# Sheet_Amp_1.net
KiCad netlist of a schematic drawn in Altium Designer
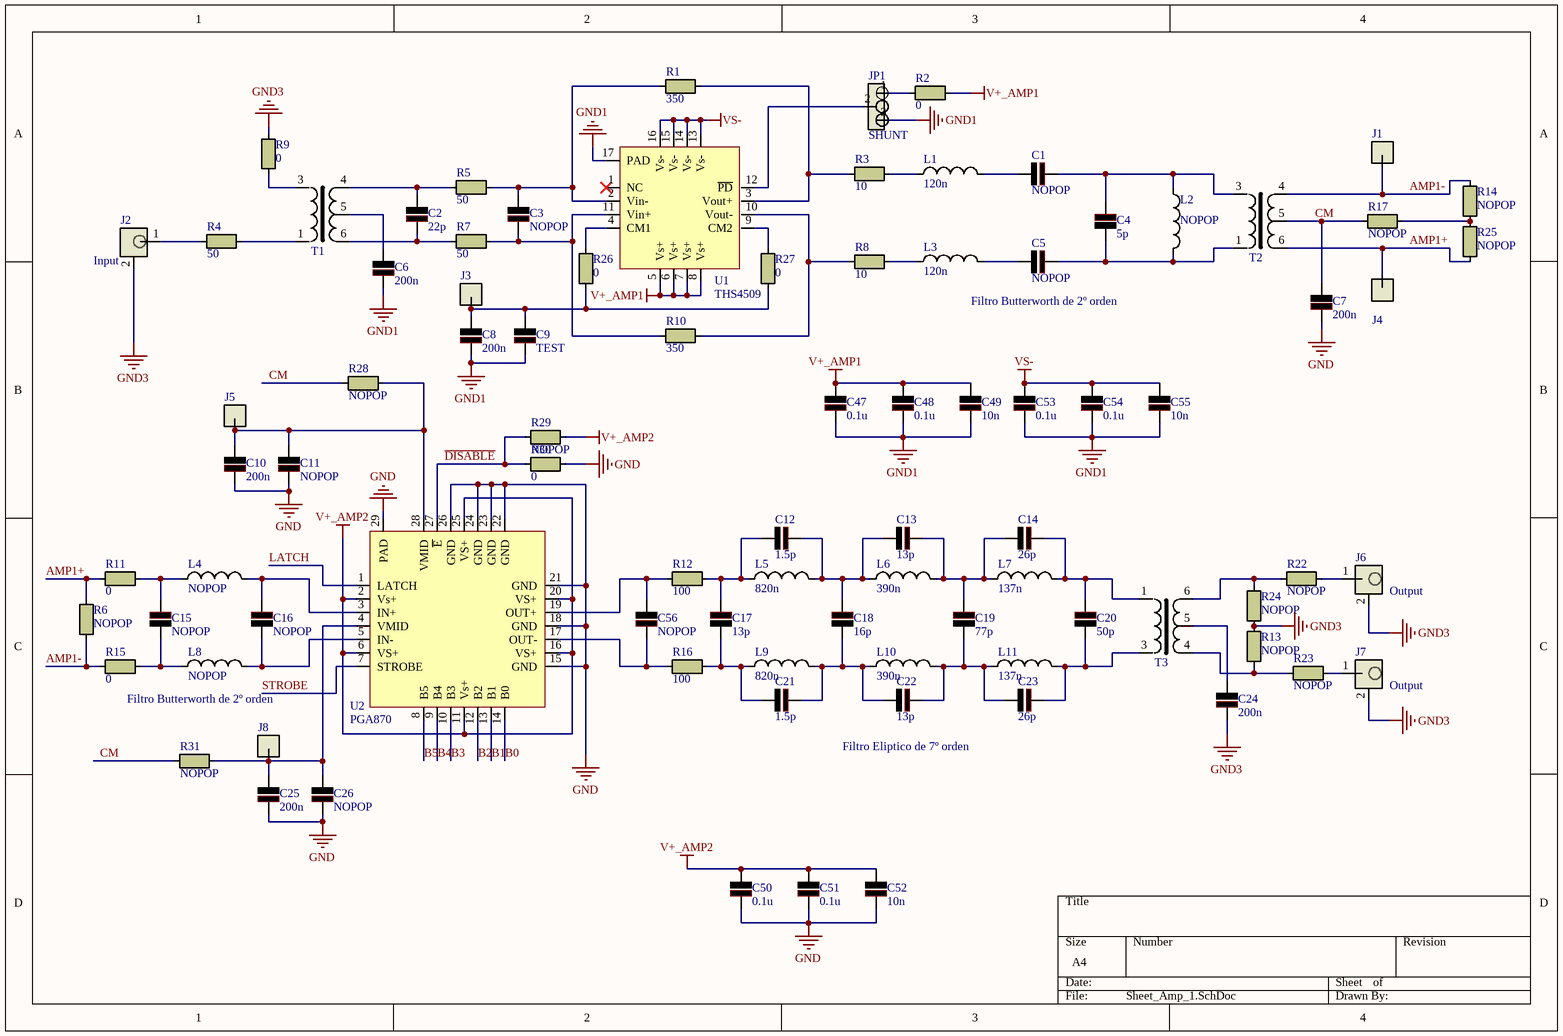
[diagram p0: Sheet_Amp_1.SchDoc]

(export (version "E")
  (design (tool "Eeschema 10.0.6"))
  (components
    (comp (ref "C1") (value "NOPOP") (footprint "C_0603") (libsource (lib "") (part "C_2")))
    (comp (ref "C2") (value "22p") (footprint "C_0603") (libsource (lib "Alberto_Sch") (part "C")))
    (comp (ref "C3") (value "NOPOP") (footprint "C_0603") (libsource (lib "Alberto_Sch") (part "C")))
    (comp (ref "C4") (value "5p") (footprint "C_0603") (libsource (lib "") (part "C_1")))
    (comp (ref "C5") (value "NOPOP") (footprint "C_0603") (libsource (lib "") (part "C_2")))
    (comp (ref "C6") (value "200n") (footprint "C_0603") (libsource (lib "Alberto_Sch") (part "C")))
    (comp (ref "C7") (value "200n") (footprint "C_0603") (libsource (lib "Alberto_Sch") (part "C")))
    (comp (ref "C8") (value "200n") (footprint "C_0805") (libsource (lib "Alberto_Sch") (part "C")))
    (comp (ref "C9") (value "TEST") (footprint "C_0805") (libsource (lib "Alberto_Sch") (part "C")))
    (comp (ref "C10") (value "200n") (footprint "C_0805") (libsource (lib "Alberto_Sch") (part "C")))
    (comp (ref "C11") (value "NOPOP") (footprint "C_0805") (libsource (lib "Alberto_Sch") (part "C")))
    (comp (ref "C12") (value "1.5p") (footprint "C_0603") (libsource (lib "") (part "C_2")))
    (comp (ref "C13") (value "13p") (footprint "C_0603") (libsource (lib "") (part "C_2")))
    (comp (ref "C14") (value "26p") (footprint "C_0603") (libsource (lib "") (part "C_2")))
    (comp (ref "C15") (value "NOPOP") (footprint "C_0603") (libsource (lib "") (part "C_1")))
    (comp (ref "C16") (value "NOPOP") (footprint "C_0603") (libsource (lib "") (part "C_1")))
    (comp (ref "C17") (value "13p") (footprint "C_0603") (libsource (lib "") (part "C_1")))
    (comp (ref "C18") (value "16p") (footprint "C_0603") (libsource (lib "") (part "C_1")))
    (comp (ref "C19") (value "77p") (footprint "C_0603") (libsource (lib "") (part "C_1")))
    (comp (ref "C20") (value "50p") (footprint "C_0603") (libsource (lib "") (part "C_1")))
    (comp (ref "C21") (value "1.5p") (footprint "C_0603") (libsource (lib "") (part "C_2")))
    (comp (ref "C22") (value "13p") (footprint "C_0603") (libsource (lib "") (part "C_2")))
    (comp (ref "C23") (value "26p") (footprint "C_0603") (libsource (lib "") (part "C_2")))
    (comp (ref "C24") (value "200n") (footprint "C_0603") (libsource (lib "Alberto_Sch") (part "C")))
    (comp (ref "C25") (value "200n") (footprint "C_0805") (libsource (lib "Alberto_Sch") (part "C")))
    (comp (ref "C26") (value "NOPOP") (footprint "C_0805") (libsource (lib "Alberto_Sch") (part "C")))
    (comp (ref "C47") (value "0.1u") (footprint "C_0805") (libsource (lib "Alberto_Sch") (part "C")))
    (comp (ref "C48") (value "0.1u") (footprint "C_0805") (libsource (lib "Alberto_Sch") (part "C")))
    (comp (ref "C49") (value "10n") (footprint "C_0805") (libsource (lib "Alberto_Sch") (part "C")))
    (comp (ref "C50") (value "0.1u") (footprint "C_0805") (libsource (lib "Alberto_Sch") (part "C")))
    (comp (ref "C51") (value "0.1u") (footprint "C_0805") (libsource (lib "Alberto_Sch") (part "C")))
    (comp (ref "C52") (value "10n") (footprint "C_0805") (libsource (lib "Alberto_Sch") (part "C")))
    (comp (ref "C53") (value "0.1u") (footprint "C_0805") (libsource (lib "Alberto_Sch") (part "C")))
    (comp (ref "C54") (value "0.1u") (footprint "C_0805") (libsource (lib "Alberto_Sch") (part "C")))
    (comp (ref "C55") (value "10n") (footprint "C_0805") (libsource (lib "Alberto_Sch") (part "C")))
    (comp (ref "C56") (value "NOPOP") (footprint "C_0603") (libsource (lib "Alberto_Sch") (part "C")))
    (comp (ref "J1")
      (value "TEST POINT")
      (footprint "TEST_Point")
      (libsource (lib "Alberto_Sch") (part "TEST POINT"))
    )
    (comp (ref "J2") (value "Input") (footprint "BNC") (libsource (lib "Alberto_Sch") (part "Input")))
    (comp (ref "J3")
      (value "TEST POINT")
      (footprint "TEST_Point")
      (libsource (lib "Alberto_Sch") (part "TEST POINT"))
    )
    (comp (ref "J4") (value "TEST POINT") (footprint "TEST_Point") (libsource (lib "") (part "TEST POINT_1")))
    (comp (ref "J5")
      (value "TEST POINT")
      (footprint "TEST_Point")
      (libsource (lib "Alberto_Sch") (part "TEST POINT"))
    )
    (comp (ref "J6") (value "Output") (footprint "SMA") (libsource (lib "Alberto_Sch") (part "Output")))
    (comp (ref "J7") (value "Output") (footprint "SMA") (libsource (lib "Alberto_Sch") (part "Output")))
    (comp (ref "J8")
      (value "TEST POINT")
      (footprint "TEST_Point")
      (libsource (lib "Alberto_Sch") (part "TEST POINT"))
    )
    (comp (ref "JP1")
      (value "SHUNT")
      (footprint "JUMPER_2,54_3")
      (libsource (lib "Alberto_Sch") (part "SHUNT"))
    )
    (comp (ref "L1") (value "120n") (footprint "L_0603") (libsource (lib "Alberto_Sch") (part "L")))
    (comp (ref "L2") (value "NOPOP") (footprint "L_0603") (libsource (lib "Alberto_Sch") (part "L")))
    (comp (ref "L3") (value "120n") (footprint "L_0603") (libsource (lib "Alberto_Sch") (part "L")))
    (comp (ref "L4") (value "NOPOP") (footprint "L_0603") (libsource (lib "Alberto_Sch") (part "L")))
    (comp (ref "L5") (value "820n") (footprint "L_0603") (libsource (lib "Alberto_Sch") (part "L")))
    (comp (ref "L6") (value "390n") (footprint "L_0603") (libsource (lib "Alberto_Sch") (part "L")))
    (comp (ref "L7") (value "137n") (footprint "L_0603") (libsource (lib "Alberto_Sch") (part "L")))
    (comp (ref "L8") (value "NOPOP") (footprint "L_0603") (libsource (lib "Alberto_Sch") (part "L")))
    (comp (ref "L9") (value "820n") (footprint "L_0603") (libsource (lib "Alberto_Sch") (part "L")))
    (comp (ref "L10") (value "390n") (footprint "L_0603") (libsource (lib "Alberto_Sch") (part "L")))
    (comp (ref "L11") (value "137n") (footprint "L_0603") (libsource (lib "Alberto_Sch") (part "L")))
    (comp (ref "R1") (value "350") (footprint "R_0603") (libsource (lib "Alberto_Sch") (part "R")))
    (comp (ref "R2") (value "0") (footprint "R_0603") (libsource (lib "Alberto_Sch") (part "R")))
    (comp (ref "R3") (value "10") (footprint "R_0603") (libsource (lib "Alberto_Sch") (part "R")))
    (comp (ref "R4") (value "50") (footprint "R_0603") (libsource (lib "Alberto_Sch") (part "R")))
    (comp (ref "R5") (value "50") (footprint "R_0603") (libsource (lib "Alberto_Sch") (part "R")))
    (comp (ref "R6") (value "NOPOP") (footprint "R_0603") (libsource (lib "") (part "R_1")))
    (comp (ref "R7") (value "50") (footprint "R_0603") (libsource (lib "Alberto_Sch") (part "R")))
    (comp (ref "R8") (value "10") (footprint "R_0603") (libsource (lib "Alberto_Sch") (part "R")))
    (comp (ref "R9") (value "0") (footprint "R_0603") (libsource (lib "") (part "R_1")))
    (comp (ref "R10") (value "350") (footprint "R_0603") (libsource (lib "Alberto_Sch") (part "R")))
    (comp (ref "R11") (value "0") (footprint "R_0603") (libsource (lib "Alberto_Sch") (part "R")))
    (comp (ref "R12") (value "100") (footprint "R_0603") (libsource (lib "Alberto_Sch") (part "R")))
    (comp (ref "R13") (value "NOPOP") (footprint "R_0603") (libsource (lib "") (part "R_1")))
    (comp (ref "R14") (value "NOPOP") (footprint "R_0603") (libsource (lib "") (part "R_1")))
    (comp (ref "R15") (value "0") (footprint "R_0603") (libsource (lib "Alberto_Sch") (part "R")))
    (comp (ref "R16") (value "100") (footprint "R_0603") (libsource (lib "Alberto_Sch") (part "R")))
    (comp (ref "R17") (value "NOPOP") (footprint "R_0603") (libsource (lib "") (part "R_2")))
    (comp (ref "R22") (value "NOPOP") (footprint "R_0603") (libsource (lib "Alberto_Sch") (part "R")))
    (comp (ref "R23") (value "NOPOP") (footprint "R_0603") (libsource (lib "Alberto_Sch") (part "R")))
    (comp (ref "R24") (value "NOPOP") (footprint "R_0603") (libsource (lib "") (part "R_1")))
    (comp (ref "R25") (value "NOPOP") (footprint "R_0603") (libsource (lib "") (part "R_1")))
    (comp (ref "R26") (value "0") (footprint "R_0603") (libsource (lib "") (part "R_1")))
    (comp (ref "R27") (value "0") (footprint "R_0603") (libsource (lib "") (part "R_1")))
    (comp (ref "R28") (value "NOPOP") (footprint "R_0603") (libsource (lib "Alberto_Sch") (part "R")))
    (comp (ref "R29") (value "NOPOP") (footprint "R_0603") (libsource (lib "Alberto_Sch") (part "R")))
    (comp (ref "R30") (value "0") (footprint "R_0603") (libsource (lib "Alberto_Sch") (part "R")))
    (comp (ref "R31") (value "NOPOP") (footprint "R_0603") (libsource (lib "Alberto_Sch") (part "R")))
    (comp (ref "T1")
      (value "ADT1-1WT")
      (footprint "TRASFORMADOR_2.54")
      (libsource (lib "Alberto_Sch") (part "Transformer_center_tab"))
    )
    (comp (ref "T2")
      (value "ADT1-1WT")
      (footprint "TRASFORMADOR_2.54")
      (libsource (lib "Alberto_Sch") (part "Transformer_center_tab"))
    )
    (comp (ref "T3")
      (value "ADT1-1WT")
      (footprint "TRASFORMADOR_2.54")
      (libsource (lib "") (part "Transformer_center_tab_1"))
    )
    (comp (ref "U1") (value "THS4509") (footprint "QFN_16") (libsource (lib "Alberto_Sch") (part "THS4509")))
    (comp (ref "U2") (value "PGA870") (footprint "QFN_28") (libsource (lib "Alberto_Sch") (part "PGA870")))
  )
  (nets
    (net (code "1") (name "/AMP1+") (class "Default")
      (node (ref "J4") (pin "1") (pinfunction "1_1") (pintype "passive"))
      (node (ref "R11") (pin "1") (pintype "passive"))
      (node (ref "R25") (pin "1") (pintype "passive"))
      (node (ref "R6") (pin "2") (pintype "passive"))
      (node (ref "T2") (pin "6") (pinfunction "6_6") (pintype "passive"))
    )
    (net (code "2") (name "/AMP1-") (class "Default")
      (node (ref "J1") (pin "1") (pinfunction "1_1") (pintype "passive"))
      (node (ref "R14") (pin "2") (pintype "passive"))
      (node (ref "R15") (pin "1") (pintype "passive"))
      (node (ref "R6") (pin "1") (pintype "passive"))
      (node (ref "T2") (pin "4") (pinfunction "4_4") (pintype "passive"))
    )
    (net (code "3") (name "/B0") (class "Default")
      (node (ref "U2") (pin "14") (pinfunction "B0_14") (pintype "passive"))
    )
    (net (code "4") (name "/B1") (class "Default")
      (node (ref "U2") (pin "13") (pinfunction "B1_13") (pintype "passive"))
    )
    (net (code "5") (name "/B2") (class "Default")
      (node (ref "U2") (pin "12") (pinfunction "B2_12") (pintype "passive"))
    )
    (net (code "6") (name "/B3") (class "Default")
      (node (ref "U2") (pin "10") (pinfunction "B3_10") (pintype "passive"))
    )
    (net (code "7") (name "/B4") (class "Default")
      (node (ref "U2") (pin "9") (pinfunction "B4_9") (pintype "passive"))
    )
    (net (code "8") (name "/B5") (class "Default")
      (node (ref "U2") (pin "8") (pinfunction "B5_8") (pintype "passive"))
    )
    (net (code "9") (name "/CM") (class "Default")
      (node (ref "C7") (pin "1") (pintype "passive"))
      (node (ref "R17") (pin "2") (pintype "passive"))
      (node (ref "R28") (pin "1") (pintype "passive"))
      (node (ref "R31") (pin "1") (pintype "passive"))
      (node (ref "T2") (pin "5") (pinfunction "5_5") (pintype "passive"))
    )
    (net (code "10") (name "/LATCH") (class "Default")
      (node (ref "U2") (pin "1") (pinfunction "LATCH_1") (pintype "passive"))
    )
    (net (code "11") (name "/STROBE") (class "Default")
      (node (ref "U2") (pin "7") (pinfunction "STROBE_7") (pintype "passive"))
    )
    (net (code "12") (name "/~{DISABLE}") (class "Default")
      (node (ref "R29") (pin "1") (pintype "passive"))
      (node (ref "R30") (pin "1") (pintype "passive"))
      (node (ref "U2") (pin "27") (pinfunction "~{E}_27") (pintype "passive"))
    )
    (net (code "13") (name "GND") (class "Default")
      (node (ref "C10") (pin "2") (pintype "passive"))
      (node (ref "C11") (pin "2") (pintype "passive"))
      (node (ref "C25") (pin "2") (pintype "passive"))
      (node (ref "C26") (pin "2") (pintype "passive"))
      (node (ref "C50") (pin "2") (pintype "passive"))
      (node (ref "C51") (pin "2") (pintype "passive"))
      (node (ref "C52") (pin "2") (pintype "passive"))
      (node (ref "C7") (pin "2") (pintype "passive"))
      (node (ref "R30") (pin "2") (pintype "passive"))
      (node (ref "U2") (pin "15") (pinfunction "GND_15") (pintype "passive"))
      (node (ref "U2") (pin "18") (pinfunction "GND_18") (pintype "passive"))
      (node (ref "U2") (pin "21") (pinfunction "GND_21") (pintype "passive"))
      (node (ref "U2") (pin "22") (pinfunction "GND_22") (pintype "passive"))
      (node (ref "U2") (pin "23") (pinfunction "GND_23") (pintype "passive"))
      (node (ref "U2") (pin "24") (pinfunction "GND_24") (pintype "passive"))
      (node (ref "U2") (pin "26") (pinfunction "GND_26") (pintype "passive"))
      (node (ref "U2") (pin "29") (pinfunction "PAD_29") (pintype "passive"))
    )
    (net (code "14") (name "GND1") (class "Default")
      (node (ref "C47") (pin "2") (pintype "passive"))
      (node (ref "C48") (pin "2") (pintype "passive"))
      (node (ref "C49") (pin "2") (pintype "passive"))
      (node (ref "C53") (pin "2") (pintype "passive"))
      (node (ref "C54") (pin "2") (pintype "passive"))
      (node (ref "C55") (pin "2") (pintype "passive"))
      (node (ref "C6") (pin "2") (pintype "passive"))
      (node (ref "C8") (pin "2") (pintype "passive"))
      (node (ref "C9") (pin "2") (pintype "passive"))
      (node (ref "JP1") (pin "3") (pinfunction "3_3") (pintype "passive"))
      (node (ref "U1") (pin "17") (pinfunction "PAD_17") (pintype "passive"))
    )
    (net (code "15") (name "GND3") (class "Default")
      (node (ref "C24") (pin "2") (pintype "passive"))
      (node (ref "J2") (pin "2") (pinfunction "2_2") (pintype "passive"))
      (node (ref "J6") (pin "2") (pinfunction "2_2") (pintype "passive"))
      (node (ref "J7") (pin "2") (pinfunction "2_2") (pintype "passive"))
      (node (ref "R13") (pin "2") (pintype "passive"))
      (node (ref "R24") (pin "1") (pintype "passive"))
      (node (ref "R9") (pin "2") (pintype "passive"))
    )
    (net (code "16") (name "Net-(C1-Pad1)") (class "Default")
      (node (ref "C1") (pin "1") (pintype "passive"))
      (node (ref "L1") (pin "2") (pintype "passive"))
    )
    (net (code "17") (name "Net-(C1-Pad2)") (class "Default")
      (node (ref "C1") (pin "2") (pintype "passive"))
      (node (ref "C4") (pin "2") (pintype "passive"))
      (node (ref "L2") (pin "1") (pintype "passive"))
      (node (ref "T2") (pin "3") (pinfunction "3_3") (pintype "passive"))
    )
    (net (code "18") (name "Net-(C2-Pad1)") (class "Default")
      (node (ref "C2") (pin "1") (pintype "passive"))
      (node (ref "R5") (pin "1") (pintype "passive"))
      (node (ref "T1") (pin "4") (pinfunction "4_4") (pintype "passive"))
    )
    (net (code "19") (name "Net-(C2-Pad2)") (class "Default")
      (node (ref "C2") (pin "2") (pintype "passive"))
      (node (ref "R7") (pin "1") (pintype "passive"))
      (node (ref "T1") (pin "6") (pinfunction "6_6") (pintype "passive"))
    )
    (net (code "20") (name "Net-(C4-Pad1)") (class "Default")
      (node (ref "C4") (pin "1") (pintype "passive"))
      (node (ref "C5") (pin "2") (pintype "passive"))
      (node (ref "L2") (pin "2") (pintype "passive"))
      (node (ref "T2") (pin "1") (pinfunction "1_1") (pintype "passive"))
    )
    (net (code "21") (name "Net-(C5-Pad1)") (class "Default")
      (node (ref "C5") (pin "1") (pintype "passive"))
      (node (ref "L3") (pin "2") (pintype "passive"))
    )
    (net (code "22") (name "Net-(C6-Pad1)") (class "Default")
      (node (ref "C6") (pin "1") (pintype "passive"))
      (node (ref "T1") (pin "5") (pinfunction "5_5") (pintype "passive"))
    )
    (net (code "23") (name "Net-(C8-Pad1)") (class "Default")
      (node (ref "C8") (pin "1") (pintype "passive"))
      (node (ref "C9") (pin "1") (pintype "passive"))
      (node (ref "J3") (pin "1") (pinfunction "1_1") (pintype "passive"))
      (node (ref "R26") (pin "1") (pintype "passive"))
      (node (ref "R27") (pin "1") (pintype "passive"))
    )
    (net (code "24") (name "Net-(C10-Pad1)") (class "Default")
      (node (ref "C10") (pin "1") (pintype "passive"))
      (node (ref "C11") (pin "1") (pintype "passive"))
      (node (ref "J5") (pin "1") (pinfunction "1_1") (pintype "passive"))
      (node (ref "R28") (pin "2") (pintype "passive"))
      (node (ref "U2") (pin "28") (pinfunction "VMID_28") (pintype "passive"))
    )
    (net (code "25") (name "Net-(C12-Pad1)") (class "Default")
      (node (ref "C12") (pin "1") (pintype "passive"))
      (node (ref "C17") (pin "2") (pintype "passive"))
      (node (ref "L5") (pin "1") (pintype "passive"))
      (node (ref "R12") (pin "2") (pintype "passive"))
    )
    (net (code "26") (name "Net-(C12-Pad2)") (class "Default")
      (node (ref "C12") (pin "2") (pintype "passive"))
      (node (ref "C13") (pin "1") (pintype "passive"))
      (node (ref "C18") (pin "2") (pintype "passive"))
      (node (ref "L5") (pin "2") (pintype "passive"))
      (node (ref "L6") (pin "1") (pintype "passive"))
    )
    (net (code "27") (name "Net-(C13-Pad2)") (class "Default")
      (node (ref "C13") (pin "2") (pintype "passive"))
      (node (ref "C14") (pin "1") (pintype "passive"))
      (node (ref "C19") (pin "2") (pintype "passive"))
      (node (ref "L6") (pin "2") (pintype "passive"))
      (node (ref "L7") (pin "1") (pintype "passive"))
    )
    (net (code "28") (name "Net-(C14-Pad2)") (class "Default")
      (node (ref "C14") (pin "2") (pintype "passive"))
      (node (ref "C20") (pin "2") (pintype "passive"))
      (node (ref "L7") (pin "2") (pintype "passive"))
      (node (ref "T3") (pin "1") (pinfunction "1_1") (pintype "passive"))
    )
    (net (code "29") (name "Net-(C15-Pad1)") (class "Default")
      (node (ref "C15") (pin "1") (pintype "passive"))
      (node (ref "L8") (pin "1") (pintype "passive"))
      (node (ref "R15") (pin "2") (pintype "passive"))
    )
    (net (code "30") (name "Net-(C15-Pad2)") (class "Default")
      (node (ref "C15") (pin "2") (pintype "passive"))
      (node (ref "L4") (pin "1") (pintype "passive"))
      (node (ref "R11") (pin "2") (pintype "passive"))
    )
    (net (code "31") (name "Net-(C17-Pad1)") (class "Default")
      (node (ref "C17") (pin "1") (pintype "passive"))
      (node (ref "C21") (pin "1") (pintype "passive"))
      (node (ref "L9") (pin "1") (pintype "passive"))
      (node (ref "R16") (pin "2") (pintype "passive"))
    )
    (net (code "32") (name "Net-(C18-Pad1)") (class "Default")
      (node (ref "C18") (pin "1") (pintype "passive"))
      (node (ref "C21") (pin "2") (pintype "passive"))
      (node (ref "C22") (pin "1") (pintype "passive"))
      (node (ref "L10") (pin "1") (pintype "passive"))
      (node (ref "L9") (pin "2") (pintype "passive"))
    )
    (net (code "33") (name "Net-(C19-Pad1)") (class "Default")
      (node (ref "C19") (pin "1") (pintype "passive"))
      (node (ref "C22") (pin "2") (pintype "passive"))
      (node (ref "C23") (pin "1") (pintype "passive"))
      (node (ref "L10") (pin "2") (pintype "passive"))
      (node (ref "L11") (pin "1") (pintype "passive"))
    )
    (net (code "34") (name "Net-(C20-Pad1)") (class "Default")
      (node (ref "C20") (pin "1") (pintype "passive"))
      (node (ref "C23") (pin "2") (pintype "passive"))
      (node (ref "L11") (pin "2") (pintype "passive"))
      (node (ref "T3") (pin "3") (pinfunction "3_3") (pintype "passive"))
    )
    (net (code "35") (name "Net-(C24-Pad1)") (class "Default")
      (node (ref "C24") (pin "1") (pintype "passive"))
      (node (ref "T3") (pin "5") (pinfunction "5_5") (pintype "passive"))
    )
    (net (code "36") (name "Net-(C25-Pad1)") (class "Default")
      (node (ref "C25") (pin "1") (pintype "passive"))
      (node (ref "C26") (pin "1") (pintype "passive"))
      (node (ref "J8") (pin "1") (pinfunction "1_1") (pintype "passive"))
      (node (ref "R31") (pin "2") (pintype "passive"))
      (node (ref "U2") (pin "4") (pinfunction "VMID_4") (pintype "passive"))
    )
    (net (code "37") (name "Net-(J2-Pad1)") (class "Default")
      (node (ref "J2") (pin "1") (pinfunction "1_1") (pintype "passive"))
      (node (ref "R4") (pin "1") (pintype "passive"))
    )
    (net (code "38") (name "Net-(J6-Pad1)") (class "Default")
      (node (ref "J6") (pin "1") (pinfunction "1_1") (pintype "passive"))
      (node (ref "R22") (pin "2") (pintype "passive"))
    )
    (net (code "39") (name "Net-(J7-Pad1)") (class "Default")
      (node (ref "J7") (pin "1") (pinfunction "1_1") (pintype "passive"))
      (node (ref "R23") (pin "2") (pintype "passive"))
    )
    (net (code "40") (name "Net-(JP1-Pad1)") (class "Default")
      (node (ref "JP1") (pin "1") (pinfunction "1_1") (pintype "passive"))
      (node (ref "R2") (pin "1") (pintype "passive"))
    )
    (net (code "41") (name "Net-(L1-Pad1)") (class "Default")
      (node (ref "L1") (pin "1") (pintype "passive"))
      (node (ref "R3") (pin "2") (pintype "passive"))
    )
    (net (code "42") (name "Net-(L3-Pad1)") (class "Default")
      (node (ref "L3") (pin "1") (pintype "passive"))
      (node (ref "R8") (pin "2") (pintype "passive"))
    )
    (net (code "43") (name "Net-(R4-Pad2)") (class "Default")
      (node (ref "R4") (pin "2") (pintype "passive"))
      (node (ref "T1") (pin "1") (pinfunction "1_1") (pintype "passive"))
    )
    (net (code "44") (name "Net-(R9-Pad1)") (class "Default")
      (node (ref "R9") (pin "1") (pintype "passive"))
      (node (ref "T1") (pin "3") (pinfunction "3_3") (pintype "passive"))
    )
    (net (code "45") (name "Net-(R13-Pad1)") (class "Default")
      (node (ref "R13") (pin "1") (pintype "passive"))
      (node (ref "R23") (pin "1") (pintype "passive"))
      (node (ref "T3") (pin "4") (pinfunction "4_4") (pintype "passive"))
    )
    (net (code "46") (name "Net-(R14-Pad1)") (class "Default")
      (node (ref "R14") (pin "1") (pintype "passive"))
      (node (ref "R17") (pin "1") (pintype "passive"))
      (node (ref "R25") (pin "2") (pintype "passive"))
    )
    (net (code "47") (name "Net-(R22-Pad1)") (class "Default")
      (node (ref "R22") (pin "1") (pintype "passive"))
      (node (ref "R24") (pin "2") (pintype "passive"))
      (node (ref "T3") (pin "6") (pinfunction "6_6") (pintype "passive"))
    )
    (net (code "48") (name "Net-(U1-CM1)") (class "Default")
      (node (ref "R26") (pin "2") (pintype "passive"))
      (node (ref "U1") (pin "4") (pinfunction "CM1_4") (pintype "passive"))
    )
    (net (code "49") (name "Net-(U1-CM2)") (class "Default")
      (node (ref "R27") (pin "2") (pintype "passive"))
      (node (ref "U1") (pin "9") (pinfunction "CM2_9") (pintype "passive"))
    )
    (net (code "50") (name "Net-(U1-Vin+)") (class "Default")
      (node (ref "C3") (pin "2") (pintype "passive"))
      (node (ref "R10") (pin "1") (pintype "passive"))
      (node (ref "R7") (pin "2") (pintype "passive"))
      (node (ref "U1") (pin "11") (pinfunction "Vin+_11") (pintype "passive"))
    )
    (net (code "51") (name "Net-(U1-Vin-)") (class "Default")
      (node (ref "C3") (pin "1") (pintype "passive"))
      (node (ref "R1") (pin "1") (pintype "passive"))
      (node (ref "R5") (pin "2") (pintype "passive"))
      (node (ref "U1") (pin "2") (pinfunction "Vin-_2") (pintype "passive"))
    )
    (net (code "52") (name "Net-(U1-Vout+)") (class "Default")
      (node (ref "R1") (pin "2") (pintype "passive"))
      (node (ref "R3") (pin "1") (pintype "passive"))
      (node (ref "U1") (pin "3") (pinfunction "Vout+_3") (pintype "passive"))
    )
    (net (code "53") (name "Net-(U1-Vout-)") (class "Default")
      (node (ref "R10") (pin "2") (pintype "passive"))
      (node (ref "R8") (pin "1") (pintype "passive"))
      (node (ref "U1") (pin "10") (pinfunction "Vout-_10") (pintype "passive"))
    )
    (net (code "54") (name "Net-(U1-~{PD})") (class "Default")
      (node (ref "JP1") (pin "2") (pinfunction "2_2") (pintype "passive"))
      (node (ref "U1") (pin "12") (pinfunction "~{PD}_12") (pintype "passive"))
    )
    (net (code "55") (name "Net-(U2-IN+)") (class "Default")
      (node (ref "C16") (pin "2") (pintype "passive"))
      (node (ref "L4") (pin "2") (pintype "passive"))
      (node (ref "U2") (pin "3") (pinfunction "IN+_3") (pintype "passive"))
    )
    (net (code "56") (name "Net-(U2-IN-)") (class "Default")
      (node (ref "C16") (pin "1") (pintype "passive"))
      (node (ref "L8") (pin "2") (pintype "passive"))
      (node (ref "U2") (pin "5") (pinfunction "IN-_5") (pintype "passive"))
    )
    (net (code "57") (name "Net-(U2-OUT+)") (class "Default")
      (node (ref "C56") (pin "1") (pintype "passive"))
      (node (ref "R12") (pin "1") (pintype "passive"))
      (node (ref "U2") (pin "19") (pinfunction "OUT+_19") (pintype "passive"))
    )
    (net (code "58") (name "Net-(U2-OUT-)") (class "Default")
      (node (ref "C56") (pin "2") (pintype "passive"))
      (node (ref "R16") (pin "1") (pintype "passive"))
      (node (ref "U2") (pin "17") (pinfunction "OUT-_17") (pintype "passive"))
    )
    (net (code "59") (name "V+_AMP1") (class "Default")
      (node (ref "C47") (pin "1") (pintype "passive"))
      (node (ref "C48") (pin "1") (pintype "passive"))
      (node (ref "C49") (pin "1") (pintype "passive"))
      (node (ref "R2") (pin "2") (pintype "passive"))
      (node (ref "U1") (pin "5") (pinfunction "Vs+_5") (pintype "passive"))
      (node (ref "U1") (pin "6") (pinfunction "Vs+_6") (pintype "passive"))
      (node (ref "U1") (pin "7") (pinfunction "Vs+_7") (pintype "passive"))
      (node (ref "U1") (pin "8") (pinfunction "Vs+_8") (pintype "passive"))
    )
    (net (code "60") (name "V+_AMP2") (class "Default")
      (node (ref "C50") (pin "1") (pintype "passive"))
      (node (ref "C51") (pin "1") (pintype "passive"))
      (node (ref "C52") (pin "1") (pintype "passive"))
      (node (ref "R29") (pin "2") (pintype "passive"))
      (node (ref "U2") (pin "11") (pinfunction "Vs+_11") (pintype "passive"))
      (node (ref "U2") (pin "16") (pinfunction "VS+_16") (pintype "passive"))
      (node (ref "U2") (pin "2") (pinfunction "Vs+_2") (pintype "passive"))
      (node (ref "U2") (pin "20") (pinfunction "VS+_20") (pintype "passive"))
      (node (ref "U2") (pin "25") (pinfunction "VS+_25") (pintype "passive"))
      (node (ref "U2") (pin "6") (pinfunction "VS+_6") (pintype "passive"))
    )
    (net (code "61") (name "VS-") (class "Default")
      (node (ref "C53") (pin "1") (pintype "passive"))
      (node (ref "C54") (pin "1") (pintype "passive"))
      (node (ref "C55") (pin "1") (pintype "passive"))
      (node (ref "U1") (pin "13") (pinfunction "Vs-_13") (pintype "passive"))
      (node (ref "U1") (pin "14") (pinfunction "Vs-_14") (pintype "passive"))
      (node (ref "U1") (pin "15") (pinfunction "Vs-_15") (pintype "passive"))
      (node (ref "U1") (pin "16") (pinfunction "Vs-_16") (pintype "passive"))
    )
    (net (code "62") (name "unconnected-(U1-NC-Pad1)") (class "Default")
      (node (ref "U1") (pin "1") (pinfunction "NC_1") (pintype "passive+no_connect"))
    )
  )
)
